# untitled.net
KiCad netlist of a schematic drawn in EAGLE
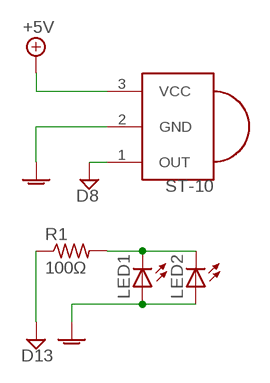
[diagram p0: schematic, sheet 1]

(export (version "E")
  (design (tool "Eeschema 10.0.6"))
  (components
    (comp (ref "LED1")
      (value "LED5MM")
      (footprint "eagle-import:LED5MM")
      (libsource (lib "eagle-import") (part "LED5MM"))
    )
    (comp (ref "LED2")
      (value "LED5MM")
      (footprint "eagle-import:LED5MM")
      (libsource (lib "eagle-import") (part "LED5MM"))
    )
    (comp (ref "R1")
      (value "100Ω")
      (footprint "eagle-import:0207_10")
      (libsource (lib "eagle-import") (part "R-US_0207/10"))
    )
    (comp (ref "ST-10")
      (value "PNA460XM")
      (footprint "eagle-import:PNA460XM")
      (libsource (lib "eagle-import") (part "PNA460XM"))
    )
  )
  (nets
    (net (code "1") (name "+5V") (class "Default")
      (node (ref "ST-10") (pin "3") (pinfunction "VCC_3") (pintype "power_in"))
    )
    (net (code "2") (name "AGND") (class "Default")
      (node (ref "LED1") (pin "A") (pinfunction "A_A") (pintype "passive"))
      (node (ref "LED2") (pin "A") (pinfunction "A_A") (pintype "passive"))
      (node (ref "ST-10") (pin "2") (pinfunction "GND_2") (pintype "power_in"))
    )
    (net (code "3") (name "D8") (class "Default")
      (node (ref "ST-10") (pin "1") (pinfunction "OUT_1") (pintype "output"))
    )
    (net (code "4") (name "D13") (class "Default")
      (node (ref "R1") (pin "1") (pinfunction "1_1") (pintype "passive"))
    )
    (net (code "5") (name "Net-(LED1-C)") (class "Default")
      (node (ref "LED1") (pin "K") (pinfunction "C_K") (pintype "passive"))
      (node (ref "LED2") (pin "K") (pinfunction "C_K") (pintype "passive"))
      (node (ref "R1") (pin "2") (pinfunction "2_2") (pintype "passive"))
    )
  )
)
